# DS132-1_0-A.net
KiCad netlist of a schematic drawn in Altium Designer
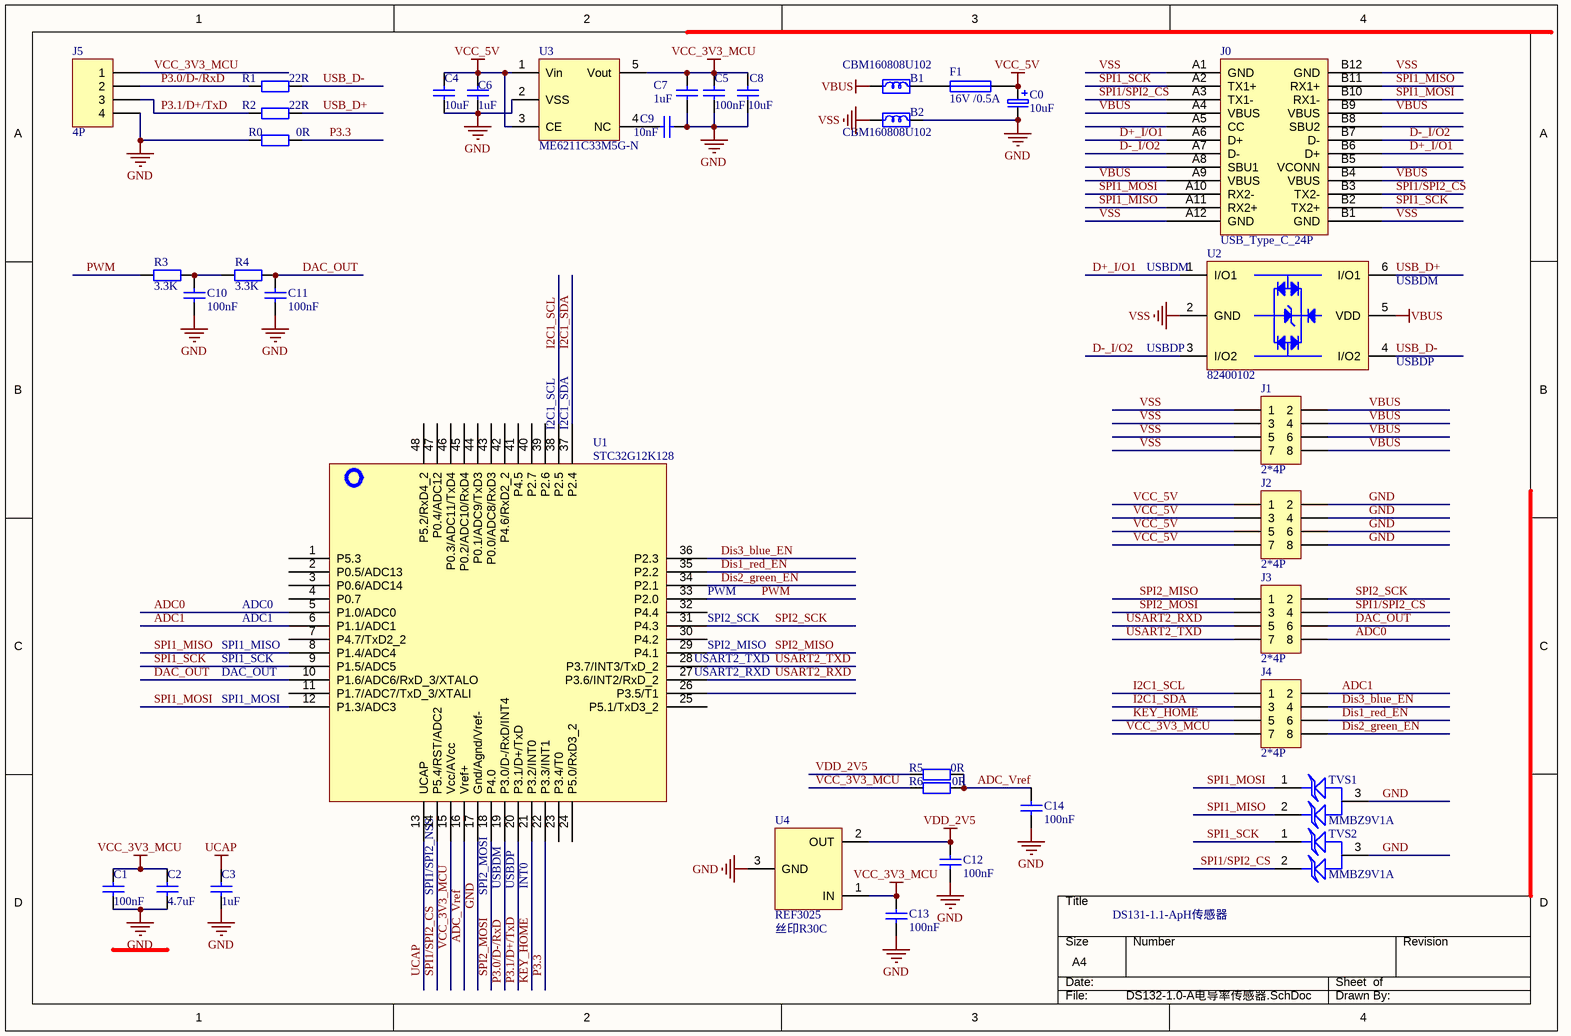
[diagram p0: DS132-1.0-A电导率传感器.SchDoc]

(export (version "E")
  (design (tool "Eeschema 10.0.6"))
  (components
    (comp (ref "B1")
      (value "CBM160808U102")
      (footprint "0603Bead")
      (description "贴片磁珠")
      (libsource (lib "AD_SCH") (part "Chip Ferrite Bead 0606"))
    )
    (comp (ref "B2")
      (value "CBM160808U102")
      (footprint "0603Bead")
      (description "贴片磁珠")
      (libsource (lib "AD_SCH") (part "Chip Ferrite Bead 0606"))
    )
    (comp (ref "C0")
      (value "10uF")
      (footprint "AVX_3216-18(1206)_SMD")
      (description "钽电容")
      (fields (field (name "Comment") "AVX_10uF/16V ±10％(C106)"))
      (libsource (lib "AD_SCH") (part "AVX_10uF/16V ±10％(C106)"))
    )
    (comp (ref "C1")
      (value "100nF")
      (footprint "0603CAP")
      (description "贴片电容")
      (fields (field (name "Comment") "SMDCAP00013"))
      (libsource (lib "AD_SCH") (part "MLCC 100nF 50V ±10％ 0603"))
    )
    (comp (ref "C2")
      (value "4.7uF")
      (footprint "0603CAP")
      (description "贴片电容")
      (fields (field (name "Comment") "SMDCAP00012"))
      (libsource (lib "AD_SCH") (part "MLCC 4.7uF 50V ±10％ 0603"))
    )
    (comp (ref "C3")
      (value "1uF")
      (footprint "0603CAP")
      (description "贴片电容")
      (fields (field (name "Comment") "SMDCAP00015"))
      (libsource (lib "AD_SCH") (part "MLCC 1uF 50V ±10％ 0603"))
    )
    (comp (ref "C4")
      (value "10uF")
      (footprint "1206CAP")
      (description "贴片电容")
      (fields (field (name "Comment") "MLCC 10uF 50V ±20％ 1206"))
      (libsource (lib "AD_SCH") (part "MLCC 10uF 50V ±20％ 1206"))
    )
    (comp (ref "C5")
      (value "100nF")
      (footprint "0603CAP")
      (description "贴片电容")
      (fields (field (name "Comment") "SMDCAP00013"))
      (libsource (lib "AD_SCH") (part "MLCC 100nF 50V ±10％ 0603"))
    )
    (comp (ref "C6")
      (value "1uF")
      (footprint "0603CAP")
      (description "贴片电容")
      (fields (field (name "Comment") "SMDCAP00015"))
      (libsource (lib "AD_SCH") (part "MLCC 1uF 50V ±10％ 0603"))
    )
    (comp (ref "C7")
      (value "1uF")
      (footprint "0603CAP")
      (description "贴片电容")
      (fields (field (name "Comment") "SMDCAP00015"))
      (libsource (lib "AD_SCH") (part "MLCC 1uF 50V ±10％ 0603"))
    )
    (comp (ref "C8")
      (value "10uF")
      (footprint "1206CAP")
      (description "贴片电容")
      (fields (field (name "Comment") "MLCC 10uF 50V ±20％ 1206"))
      (libsource (lib "AD_SCH") (part "MLCC 10uF 50V ±20％ 1206"))
    )
    (comp (ref "C9")
      (value "10nF")
      (footprint "0603CAP")
      (description "贴片电容")
      (fields (field (name "Comment") "SMDCAP00010"))
      (libsource (lib "AD_SCH") (part "MLCC 10nF 50V ±10％ 0603"))
    )
    (comp (ref "C10")
      (value "100nF")
      (footprint "0603CAP")
      (description "贴片电容")
      (fields (field (name "Comment") "SMDCAP00013"))
      (libsource (lib "AD_SCH") (part "MLCC 100nF 50V ±10％ 0603"))
    )
    (comp (ref "C11")
      (value "100nF")
      (footprint "0603CAP")
      (description "贴片电容")
      (fields (field (name "Comment") "SMDCAP00013"))
      (libsource (lib "AD_SCH") (part "MLCC 100nF 50V ±10％ 0603"))
    )
    (comp (ref "C12")
      (value "100nF")
      (footprint "0603CAP")
      (description "贴片电容")
      (fields (field (name "Comment") "SMDCAP00013"))
      (libsource (lib "AD_SCH") (part "MLCC 100nF 50V ±10％ 0603"))
    )
    (comp (ref "C13")
      (value "100nF")
      (footprint "0603CAP")
      (description "贴片电容")
      (fields (field (name "Comment") "SMDCAP00013"))
      (libsource (lib "AD_SCH") (part "MLCC 100nF 50V ±10％ 0603"))
    )
    (comp (ref "C14")
      (value "100nF")
      (footprint "0603CAP")
      (description "贴片电容")
      (fields (field (name "Comment") "SMDCAP00013"))
      (libsource (lib "AD_SCH") (part "MLCC 100nF 50V ±10％ 0603"))
    )
    (comp (ref "F1")
      (value "16V /0.5A")
      (footprint "1206FUSE")
      (description "贴片自恢复保险丝 16V /0.5A")
      (fields (field (name "Comment") "SMD1206-050C-16V"))
      (libsource (lib "AD_SCH") (part "SMD1206-050C-16V"))
    )
    (comp (ref "J0")
      (value "USB_Type_C_24P")
      (footprint "USB_TYPE_C_24P_Receptacle")
      (libsource (lib "AD_SCH") (part "USB_Type_C_24P"))
    )
    (comp (ref "J1")
      (value "2*4P")
      (footprint "X1321FVS-2x04-C43D48")
      (description "双排母2x4P 立贴 1.27mm")
      (fields (field (name "Comment") "X1321FVS-2x04-C43D48"))
      (libsource (lib "AD_SCH") (part "X1321FVS-2x04-C43D48"))
    )
    (comp (ref "J2")
      (value "2*4P")
      (footprint "X1321FVS-2x04-C43D48")
      (description "双排母2x4P 立贴 1.27mm")
      (fields (field (name "Comment") "X1321FVS-2x04-C43D48"))
      (libsource (lib "AD_SCH") (part "X1321FVS-2x04-C43D48"))
    )
    (comp (ref "J3")
      (value "2*4P")
      (footprint "X1321FVS-2x04-C43D48")
      (description "双排母2x4P 立贴 1.27mm")
      (fields (field (name "Comment") "X1321FVS-2x04-C43D48"))
      (libsource (lib "AD_SCH") (part "X1321FVS-2x04-C43D48"))
    )
    (comp (ref "J4")
      (value "2*4P")
      (footprint "X1321FVS-2x04-C43D48")
      (description "双排母2x4P 立贴 1.27mm")
      (fields (field (name "Comment") "X1321FVS-2x04-C43D48"))
      (libsource (lib "AD_SCH") (part "X1321FVS-2x04-C43D48"))
    )
    (comp (ref "J5")
      (value "4P")
      (footprint "H4")
      (description "单排直针")
      (fields (field (name "Comment") "DIP4单排直针  间距2mm 针长11mm 铜"))
      (libsource (lib "AD_SCH") (part "DIP4单排直针  间距2mm 针长11mm 铜"))
    )
    (comp (ref "R0")
      (value "0R")
      (footprint "0603RES")
      (description "贴片电阻")
      (fields (field (name "Comment") "Chip 0R 1/16W ±1％ 0603"))
      (libsource (lib "AD_SCH") (part "Chip 0R 1/16W ±1％ 0603"))
    )
    (comp (ref "R1")
      (value "22R")
      (footprint "0603RES")
      (description "贴片电阻")
      (fields (field (name "Comment") "Chip 22R 1/16W ±1％ 0603"))
      (libsource (lib "AD_SCH") (part "Chip 22R 1/16W ±1％ 0603"))
    )
    (comp (ref "R2")
      (value "22R")
      (footprint "0603RES")
      (description "贴片电阻")
      (fields (field (name "Comment") "Chip 22R 1/16W ±1％ 0603"))
      (libsource (lib "AD_SCH") (part "Chip 22R 1/16W ±1％ 0603"))
    )
    (comp (ref "R3")
      (value "3.3K")
      (footprint "0603RES")
      (description "贴片电阻")
      (fields (field (name "Comment") "SMDRES00090"))
      (libsource (lib "AD_SCH") (part "Chip 3.3K 1/16W ±1％ 0603"))
    )
    (comp (ref "R4")
      (value "3.3K")
      (footprint "0603RES")
      (description "贴片电阻")
      (fields (field (name "Comment") "SMDRES00090"))
      (libsource (lib "AD_SCH") (part "Chip 3.3K 1/16W ±1％ 0603"))
    )
    (comp (ref "R5")
      (value "0R")
      (footprint "0603RES")
      (description "贴片电阻")
      (fields (field (name "Comment") "Chip 0R 1/16W ±1％ 0603"))
      (libsource (lib "AD_SCH") (part "Chip 0R 1/16W ±1％ 0603"))
    )
    (comp (ref "R6")
      (value "0R")
      (footprint "0603RES")
      (description "贴片电阻")
      (fields (field (name "Comment") "Chip 0R 1/16W ±1％ 0603"))
      (libsource (lib "AD_SCH") (part "Chip 0R 1/16W ±1％ 0603"))
    )
    (comp (ref "TVS1")
      (value "MMBZ9V1A")
      (footprint "SOT23")
      (description "瞬态抑制二极管")
      (libsource (lib "AD_SCH") (part "TVS"))
    )
    (comp (ref "TVS2")
      (value "MMBZ9V1A")
      (footprint "SOT23")
      (description "瞬态抑制二极管")
      (libsource (lib "AD_SCH") (part "TVS"))
    )
    (comp (ref "U1")
      (value "STC32G12K128")
      (footprint "LQFP-48")
      (description "单片机芯片")
      (fields (field (name "Comment") "STC32G12K128_35I LQFP48"))
      (libsource (lib "AD_SCH") (part "STC32G12K128_35I LQFP48"))
    )
    (comp (ref "U2")
      (value "82400102")
      (footprint "SOT23-6")
      (description "瞬态抑制二极管(TVS)")
      (libsource (lib "AD_SCH") (part "82400102"))
    )
    (comp (ref "U3")
      (value "ME6211C33M5G-N")
      (footprint "SOT23-5")
      (description "稳压芯片")
      (libsource (lib "AD_SCH") (part "ME6211C33M5G-N"))
    )
    (comp (ref "U4")
      (value "REF3025")
      (footprint "SOT23")
      (fields (field (name "ALTIUM_VALUE") "丝印R30C"))
      (libsource (lib "AD_SCH") (part "REF3025"))
    )
  )
  (nets
    (net (code "1") (name "/ADC0") (class "Default")
      (node (ref "J3") (pin "8") (pinfunction "8_8") (pintype "passive"))
      (node (ref "U1") (pin "5") (pinfunction "P1.0/ADC0_5") (pintype "passive"))
    )
    (net (code "2") (name "/ADC1") (class "Default")
      (node (ref "J4") (pin "2") (pinfunction "2_2") (pintype "passive"))
      (node (ref "U1") (pin "6") (pinfunction "P1.1/ADC1_6") (pintype "passive"))
    )
    (net (code "3") (name "/ADC_Vref") (class "Default")
      (node (ref "C14") (pin "2") (pinfunction "2_2") (pintype "passive"))
      (node (ref "R5") (pin "2") (pinfunction "2_2") (pintype "passive"))
      (node (ref "R6") (pin "2") (pinfunction "2_2") (pintype "passive"))
      (node (ref "U1") (pin "16") (pinfunction "Vref+_16") (pintype "passive"))
    )
    (net (code "4") (name "/D+_I{slash}O1") (class "Default")
      (node (ref "J0") (pin "A6") (pinfunction "D+_A6") (pintype "passive"))
      (node (ref "J0") (pin "B6") (pinfunction "D+_B6") (pintype "passive"))
      (node (ref "U2") (pin "1") (pinfunction "I/O1_1") (pintype "passive"))
    )
    (net (code "5") (name "/D-_I{slash}O2") (class "Default")
      (node (ref "J0") (pin "A7") (pinfunction "D-_A7") (pintype "passive"))
      (node (ref "J0") (pin "B7") (pinfunction "D-_B7") (pintype "passive"))
      (node (ref "U2") (pin "3") (pinfunction "I/O2_3") (pintype "passive"))
    )
    (net (code "6") (name "/DAC_OUT") (class "Default")
      (node (ref "C11") (pin "2") (pinfunction "2_2") (pintype "passive"))
      (node (ref "J3") (pin "6") (pinfunction "6_6") (pintype "passive"))
      (node (ref "R4") (pin "2") (pinfunction "2_2") (pintype "passive"))
      (node (ref "U1") (pin "10") (pinfunction "P1.6/ADC6/RxD_3/XTALO_10") (pintype "passive"))
    )
    (net (code "7") (name "/Dis1_red_EN") (class "Default")
      (node (ref "J4") (pin "6") (pinfunction "6_6") (pintype "passive"))
      (node (ref "U1") (pin "35") (pinfunction "P2.2_35") (pintype "passive"))
    )
    (net (code "8") (name "/Dis2_green_EN") (class "Default")
      (node (ref "J4") (pin "8") (pinfunction "8_8") (pintype "passive"))
      (node (ref "U1") (pin "34") (pinfunction "P2.1_34") (pintype "passive"))
    )
    (net (code "9") (name "/Dis3_blue_EN") (class "Default")
      (node (ref "J4") (pin "4") (pinfunction "4_4") (pintype "passive"))
      (node (ref "U1") (pin "36") (pinfunction "P2.3_36") (pintype "passive"))
    )
    (net (code "10") (name "/I2C1_SCL") (class "Default")
      (node (ref "J4") (pin "1") (pinfunction "1_1") (pintype "passive"))
      (node (ref "U1") (pin "38") (pinfunction "P2.5_38") (pintype "passive"))
    )
    (net (code "11") (name "/I2C1_SDA") (class "Default")
      (node (ref "J4") (pin "3") (pinfunction "3_3") (pintype "passive"))
      (node (ref "U1") (pin "37") (pinfunction "P2.4_37") (pintype "passive"))
    )
    (net (code "12") (name "/KEY_HOME") (class "Default")
      (node (ref "J4") (pin "5") (pinfunction "5_5") (pintype "passive"))
      (node (ref "U1") (pin "21") (pinfunction "P3.2/INT0_21") (pintype "passive"))
    )
    (net (code "13") (name "/P3.0{slash}D-{slash}RxD") (class "Default")
      (node (ref "J5") (pin "2") (pinfunction "2_2") (pintype "passive"))
      (node (ref "R1") (pin "1") (pinfunction "1_1") (pintype "passive"))
      (node (ref "U1") (pin "19") (pinfunction "P3.0/D-/RxD/INT4_19") (pintype "passive"))
    )
    (net (code "14") (name "/P3.1{slash}D+{slash}TxD") (class "Default")
      (node (ref "J5") (pin "3") (pinfunction "3_3") (pintype "passive"))
      (node (ref "R2") (pin "1") (pinfunction "1_1") (pintype "passive"))
      (node (ref "U1") (pin "20") (pinfunction "P3.1/D+/TxD_20") (pintype "passive"))
    )
    (net (code "15") (name "/P3.3") (class "Default")
      (node (ref "R0") (pin "2") (pinfunction "2_2") (pintype "passive"))
      (node (ref "U1") (pin "22") (pinfunction "P3.3/INT1_22") (pintype "passive"))
    )
    (net (code "16") (name "/PWM") (class "Default")
      (node (ref "R3") (pin "1") (pinfunction "1_1") (pintype "passive"))
      (node (ref "U1") (pin "33") (pinfunction "P2.0_33") (pintype "passive"))
    )
    (net (code "17") (name "/SPI1_MISO") (class "Default")
      (node (ref "J0") (pin "A11") (pinfunction "RX2+_A11") (pintype "passive"))
      (node (ref "J0") (pin "B11") (pinfunction "RX1+_B11") (pintype "passive"))
      (node (ref "TVS1") (pin "2") (pinfunction "2_2") (pintype "passive"))
      (node (ref "U1") (pin "8") (pinfunction "P1.4/ADC4_8") (pintype "passive"))
    )
    (net (code "18") (name "/SPI1_MOSI") (class "Default")
      (node (ref "J0") (pin "A10") (pinfunction "RX2-_A10") (pintype "passive"))
      (node (ref "J0") (pin "B10") (pinfunction "RX1-_B10") (pintype "passive"))
      (node (ref "TVS1") (pin "1") (pinfunction "1_1") (pintype "passive"))
      (node (ref "U1") (pin "12") (pinfunction "P1.3/ADC3_12") (pintype "passive"))
    )
    (net (code "19") (name "/SPI1_SCK") (class "Default")
      (node (ref "J0") (pin "A2") (pinfunction "TX1+_A2") (pintype "passive"))
      (node (ref "J0") (pin "B2") (pinfunction "TX2+_B2") (pintype "passive"))
      (node (ref "TVS2") (pin "1") (pinfunction "1_1") (pintype "passive"))
      (node (ref "U1") (pin "9") (pinfunction "P1.5/ADC5_9") (pintype "passive"))
    )
    (net (code "20") (name "/SPI1{slash}SPI2_CS") (class "Default")
      (node (ref "J0") (pin "A3") (pinfunction "TX1-_A3") (pintype "passive"))
      (node (ref "J0") (pin "B3") (pinfunction "TX2-_B3") (pintype "passive"))
      (node (ref "J3") (pin "4") (pinfunction "4_4") (pintype "passive"))
      (node (ref "TVS2") (pin "2") (pinfunction "2_2") (pintype "passive"))
      (node (ref "U1") (pin "14") (pinfunction "P5.4/RST/ADC2_14") (pintype "passive"))
    )
    (net (code "21") (name "/SPI2_MISO") (class "Default")
      (node (ref "J3") (pin "1") (pinfunction "1_1") (pintype "passive"))
      (node (ref "U1") (pin "29") (pinfunction "P4.1_29") (pintype "passive"))
    )
    (net (code "22") (name "/SPI2_MOSI") (class "Default")
      (node (ref "J3") (pin "3") (pinfunction "3_3") (pintype "passive"))
      (node (ref "U1") (pin "18") (pinfunction "P4.0_18") (pintype "passive"))
    )
    (net (code "23") (name "/SPI2_SCK") (class "Default")
      (node (ref "J3") (pin "2") (pinfunction "2_2") (pintype "passive"))
      (node (ref "U1") (pin "31") (pinfunction "P4.3_31") (pintype "passive"))
    )
    (net (code "24") (name "/USART2_RXD") (class "Default")
      (node (ref "J3") (pin "5") (pinfunction "5_5") (pintype "passive"))
      (node (ref "U1") (pin "27") (pinfunction "P3.6/INT2/RxD_2_27") (pintype "passive"))
    )
    (net (code "25") (name "/USART2_TXD") (class "Default")
      (node (ref "J3") (pin "7") (pinfunction "7_7") (pintype "passive"))
      (node (ref "U1") (pin "28") (pinfunction "P3.7/INT3/TxD_2_28") (pintype "passive"))
    )
    (net (code "26") (name "/USB_D+") (class "Default")
      (node (ref "R2") (pin "2") (pinfunction "2_2") (pintype "passive"))
      (node (ref "U2") (pin "6") (pinfunction "I/O1_6") (pintype "passive"))
    )
    (net (code "27") (name "/USB_D-") (class "Default")
      (node (ref "R1") (pin "2") (pinfunction "2_2") (pintype "passive"))
      (node (ref "U2") (pin "4") (pinfunction "I/O2_4") (pintype "passive"))
    )
    (net (code "28") (name "GND") (class "Default")
      (node (ref "B2") (pin "2") (pinfunction "2_2") (pintype "passive"))
      (node (ref "C0") (pin "2") (pinfunction "2_2") (pintype "passive"))
      (node (ref "C1") (pin "1") (pinfunction "1_1") (pintype "passive"))
      (node (ref "C10") (pin "1") (pinfunction "1_1") (pintype "passive"))
      (node (ref "C11") (pin "1") (pinfunction "1_1") (pintype "passive"))
      (node (ref "C12") (pin "1") (pinfunction "1_1") (pintype "passive"))
      (node (ref "C13") (pin "1") (pinfunction "1_1") (pintype "passive"))
      (node (ref "C14") (pin "1") (pinfunction "1_1") (pintype "passive"))
      (node (ref "C2") (pin "1") (pinfunction "1_1") (pintype "passive"))
      (node (ref "C3") (pin "1") (pinfunction "1_1") (pintype "passive"))
      (node (ref "C4") (pin "1") (pinfunction "1_1") (pintype "passive"))
      (node (ref "C5") (pin "1") (pinfunction "1_1") (pintype "passive"))
      (node (ref "C6") (pin "1") (pinfunction "1_1") (pintype "passive"))
      (node (ref "C7") (pin "1") (pinfunction "1_1") (pintype "passive"))
      (node (ref "C8") (pin "1") (pinfunction "1_1") (pintype "passive"))
      (node (ref "C9") (pin "2") (pinfunction "2_2") (pintype "passive"))
      (node (ref "J2") (pin "2") (pinfunction "2_2") (pintype "passive"))
      (node (ref "J2") (pin "4") (pinfunction "4_4") (pintype "passive"))
      (node (ref "J2") (pin "6") (pinfunction "6_6") (pintype "passive"))
      (node (ref "J2") (pin "8") (pinfunction "8_8") (pintype "passive"))
      (node (ref "J5") (pin "4") (pinfunction "4_4") (pintype "passive"))
      (node (ref "R0") (pin "1") (pinfunction "1_1") (pintype "passive"))
      (node (ref "TVS1") (pin "3") (pinfunction "3_3") (pintype "passive"))
      (node (ref "TVS2") (pin "3") (pinfunction "3_3") (pintype "passive"))
      (node (ref "U1") (pin "17") (pinfunction "Gnd/Agnd/Vref-_17") (pintype "passive"))
      (node (ref "U3") (pin "2") (pinfunction "VSS_2") (pintype "passive"))
      (node (ref "U4") (pin "3") (pinfunction "GND_3") (pintype "passive"))
    )
    (net (code "29") (name "Net-(B1-Pad2)") (class "Default")
      (node (ref "B1") (pin "2") (pinfunction "2_2") (pintype "passive"))
      (node (ref "F1") (pin "1") (pinfunction "1_1") (pintype "passive"))
    )
    (net (code "30") (name "Net-(C10-Pad2)") (class "Default")
      (node (ref "C10") (pin "2") (pinfunction "2_2") (pintype "passive"))
      (node (ref "R3") (pin "2") (pinfunction "2_2") (pintype "passive"))
      (node (ref "R4") (pin "1") (pinfunction "1_1") (pintype "passive"))
    )
    (net (code "31") (name "Net-(U3-NC)") (class "Default")
      (node (ref "C9") (pin "1") (pinfunction "1_1") (pintype "passive"))
      (node (ref "U3") (pin "4") (pinfunction "NC_4") (pintype "passive"))
    )
    (net (code "32") (name "UCAP") (class "Default")
      (node (ref "C3") (pin "2") (pinfunction "2_2") (pintype "passive"))
      (node (ref "U1") (pin "13") (pinfunction "UCAP_13") (pintype "passive"))
    )
    (net (code "33") (name "VBUS") (class "Default")
      (node (ref "B1") (pin "1") (pinfunction "1_1") (pintype "passive"))
      (node (ref "J0") (pin "A4") (pinfunction "VBUS_A4") (pintype "passive"))
      (node (ref "J0") (pin "A9") (pinfunction "VBUS_A9") (pintype "passive"))
      (node (ref "J0") (pin "B4") (pinfunction "VBUS_B4") (pintype "passive"))
      (node (ref "J0") (pin "B9") (pinfunction "VBUS_B9") (pintype "passive"))
      (node (ref "J1") (pin "2") (pinfunction "2_2") (pintype "passive"))
      (node (ref "J1") (pin "4") (pinfunction "4_4") (pintype "passive"))
      (node (ref "J1") (pin "6") (pinfunction "6_6") (pintype "passive"))
      (node (ref "J1") (pin "8") (pinfunction "8_8") (pintype "passive"))
      (node (ref "U2") (pin "5") (pinfunction "VDD_5") (pintype "passive"))
    )
    (net (code "34") (name "VCC_3V3_MCU") (class "Default")
      (node (ref "C1") (pin "2") (pinfunction "2_2") (pintype "passive"))
      (node (ref "C13") (pin "2") (pinfunction "2_2") (pintype "passive"))
      (node (ref "C2") (pin "2") (pinfunction "2_2") (pintype "passive"))
      (node (ref "C5") (pin "2") (pinfunction "2_2") (pintype "passive"))
      (node (ref "C7") (pin "2") (pinfunction "2_2") (pintype "passive"))
      (node (ref "C8") (pin "2") (pinfunction "2_2") (pintype "passive"))
      (node (ref "J4") (pin "7") (pinfunction "7_7") (pintype "passive"))
      (node (ref "J5") (pin "1") (pinfunction "1_1") (pintype "passive"))
      (node (ref "R6") (pin "1") (pinfunction "1_1") (pintype "passive"))
      (node (ref "U1") (pin "15") (pinfunction "Vcc/AVcc_15") (pintype "passive"))
      (node (ref "U3") (pin "5") (pinfunction "Vout_5") (pintype "passive"))
      (node (ref "U4") (pin "1") (pinfunction "IN_1") (pintype "passive"))
    )
    (net (code "35") (name "VCC_5V") (class "Default")
      (node (ref "C0") (pin "1") (pinfunction "1_1") (pintype "passive"))
      (node (ref "C4") (pin "2") (pinfunction "2_2") (pintype "passive"))
      (node (ref "C6") (pin "2") (pinfunction "2_2") (pintype "passive"))
      (node (ref "F1") (pin "2") (pinfunction "2_2") (pintype "passive"))
      (node (ref "J2") (pin "1") (pinfunction "1_1") (pintype "passive"))
      (node (ref "J2") (pin "3") (pinfunction "3_3") (pintype "passive"))
      (node (ref "J2") (pin "5") (pinfunction "5_5") (pintype "passive"))
      (node (ref "J2") (pin "7") (pinfunction "7_7") (pintype "passive"))
      (node (ref "U3") (pin "1") (pinfunction "Vin_1") (pintype "passive"))
      (node (ref "U3") (pin "3") (pinfunction "CE_3") (pintype "passive"))
    )
    (net (code "36") (name "VDD_2V5") (class "Default")
      (node (ref "C12") (pin "2") (pinfunction "2_2") (pintype "passive"))
      (node (ref "R5") (pin "1") (pinfunction "1_1") (pintype "passive"))
      (node (ref "U4") (pin "2") (pinfunction "OUT_2") (pintype "passive"))
    )
    (net (code "37") (name "VSS") (class "Default")
      (node (ref "B2") (pin "1") (pinfunction "1_1") (pintype "passive"))
      (node (ref "J0") (pin "A1") (pinfunction "GND_A1") (pintype "passive"))
      (node (ref "J0") (pin "A12") (pinfunction "GND_A12") (pintype "passive"))
      (node (ref "J0") (pin "B1") (pinfunction "GND_B1") (pintype "passive"))
      (node (ref "J0") (pin "B12") (pinfunction "GND_B12") (pintype "passive"))
      (node (ref "J1") (pin "1") (pinfunction "1_1") (pintype "passive"))
      (node (ref "J1") (pin "3") (pinfunction "3_3") (pintype "passive"))
      (node (ref "J1") (pin "5") (pinfunction "5_5") (pintype "passive"))
      (node (ref "J1") (pin "7") (pinfunction "7_7") (pintype "passive"))
      (node (ref "U2") (pin "2") (pinfunction "GND_2") (pintype "passive"))
    )
    (net (code "38") (name "unconnected-(J0-CC-PadA5)") (class "Default")
      (node (ref "J0") (pin "A5") (pinfunction "CC_A5") (pintype "passive"))
    )
    (net (code "39") (name "unconnected-(J0-SBU1-PadA8)") (class "Default")
      (node (ref "J0") (pin "A8") (pinfunction "SBU1_A8") (pintype "passive"))
    )
    (net (code "40") (name "unconnected-(J0-SBU2-PadB8)") (class "Default")
      (node (ref "J0") (pin "B8") (pinfunction "SBU2_B8") (pintype "passive"))
    )
    (net (code "41") (name "unconnected-(J0-VCONN-PadB5)") (class "Default")
      (node (ref "J0") (pin "B5") (pinfunction "VCONN_B5") (pintype "passive"))
    )
    (net (code "42") (name "unconnected-(U1-P0.0{slash}ADC8{slash}RxD3-Pad43)") (class "Default")
      (node (ref "U1") (pin "43") (pinfunction "P0.0/ADC8/RxD3_43") (pintype "passive"))
    )
    (net (code "43") (name "unconnected-(U1-P0.1{slash}ADC9{slash}TxD3-Pad44)") (class "Default")
      (node (ref "U1") (pin "44") (pinfunction "P0.1/ADC9/TxD3_44") (pintype "passive"))
    )
    (net (code "44") (name "unconnected-(U1-P0.2{slash}ADC10{slash}RxD4-Pad45)") (class "Default")
      (node (ref "U1") (pin "45") (pinfunction "P0.2/ADC10/RxD4_45") (pintype "passive"))
    )
    (net (code "45") (name "unconnected-(U1-P0.3{slash}ADC11{slash}TxD4-Pad46)") (class "Default")
      (node (ref "U1") (pin "46") (pinfunction "P0.3/ADC11/TxD4_46") (pintype "passive"))
    )
    (net (code "46") (name "unconnected-(U1-P0.4{slash}ADC12-Pad47)") (class "Default")
      (node (ref "U1") (pin "47") (pinfunction "P0.4/ADC12_47") (pintype "passive"))
    )
    (net (code "47") (name "unconnected-(U1-P0.5{slash}ADC13-Pad2)") (class "Default")
      (node (ref "U1") (pin "2") (pinfunction "P0.5/ADC13_2") (pintype "passive"))
    )
    (net (code "48") (name "unconnected-(U1-P0.6{slash}ADC14-Pad3)") (class "Default")
      (node (ref "U1") (pin "3") (pinfunction "P0.6/ADC14_3") (pintype "passive"))
    )
    (net (code "49") (name "unconnected-(U1-P0.7-Pad4)") (class "Default")
      (node (ref "U1") (pin "4") (pinfunction "P0.7_4") (pintype "passive"))
    )
    (net (code "50") (name "unconnected-(U1-P1.7{slash}ADC7{slash}TxD_3{slash}XTALI-Pad11)") (class "Default")
      (node (ref "U1") (pin "11") (pinfunction "P1.7/ADC7/TxD_3/XTALI_11") (pintype "passive"))
    )
    (net (code "51") (name "unconnected-(U1-P2.6-Pad39)") (class "Default")
      (node (ref "U1") (pin "39") (pinfunction "P2.6_39") (pintype "passive"))
    )
    (net (code "52") (name "unconnected-(U1-P2.7-Pad40)") (class "Default")
      (node (ref "U1") (pin "40") (pinfunction "P2.7_40") (pintype "passive"))
    )
    (net (code "53") (name "unconnected-(U1-P3.4{slash}T0-Pad23)") (class "Default")
      (node (ref "U1") (pin "23") (pinfunction "P3.4/T0_23") (pintype "passive"))
    )
    (net (code "54") (name "unconnected-(U1-P3.5{slash}T1-Pad26)") (class "Default")
      (node (ref "U1") (pin "26") (pinfunction "P3.5/T1_26") (pintype "passive"))
    )
    (net (code "55") (name "unconnected-(U1-P4.2-Pad30)") (class "Default")
      (node (ref "U1") (pin "30") (pinfunction "P4.2_30") (pintype "passive"))
    )
    (net (code "56") (name "unconnected-(U1-P4.4-Pad32)") (class "Default")
      (node (ref "U1") (pin "32") (pinfunction "P4.4_32") (pintype "passive"))
    )
    (net (code "57") (name "unconnected-(U1-P4.5-Pad41)") (class "Default")
      (node (ref "U1") (pin "41") (pinfunction "P4.5_41") (pintype "passive"))
    )
    (net (code "58") (name "unconnected-(U1-P4.6{slash}RxD2_2-Pad42)") (class "Default")
      (node (ref "U1") (pin "42") (pinfunction "P4.6/RxD2_2_42") (pintype "passive"))
    )
    (net (code "59") (name "unconnected-(U1-P4.7{slash}TxD2_2-Pad7)") (class "Default")
      (node (ref "U1") (pin "7") (pinfunction "P4.7/TxD2_2_7") (pintype "passive"))
    )
    (net (code "60") (name "unconnected-(U1-P5.0{slash}RxD3_2-Pad24)") (class "Default")
      (node (ref "U1") (pin "24") (pinfunction "P5.0/RxD3_2_24") (pintype "passive"))
    )
    (net (code "61") (name "unconnected-(U1-P5.1{slash}TxD3_2-Pad25)") (class "Default")
      (node (ref "U1") (pin "25") (pinfunction "P5.1/TxD3_2_25") (pintype "passive"))
    )
    (net (code "62") (name "unconnected-(U1-P5.2{slash}RxD4_2-Pad48)") (class "Default")
      (node (ref "U1") (pin "48") (pinfunction "P5.2/RxD4_2_48") (pintype "passive"))
    )
    (net (code "63") (name "unconnected-(U1-P5.3-Pad1)") (class "Default")
      (node (ref "U1") (pin "1") (pinfunction "P5.3_1") (pintype "passive"))
    )
  )
)
